# exp2_1.net
KiCad netlist of a schematic drawn in EAGLE
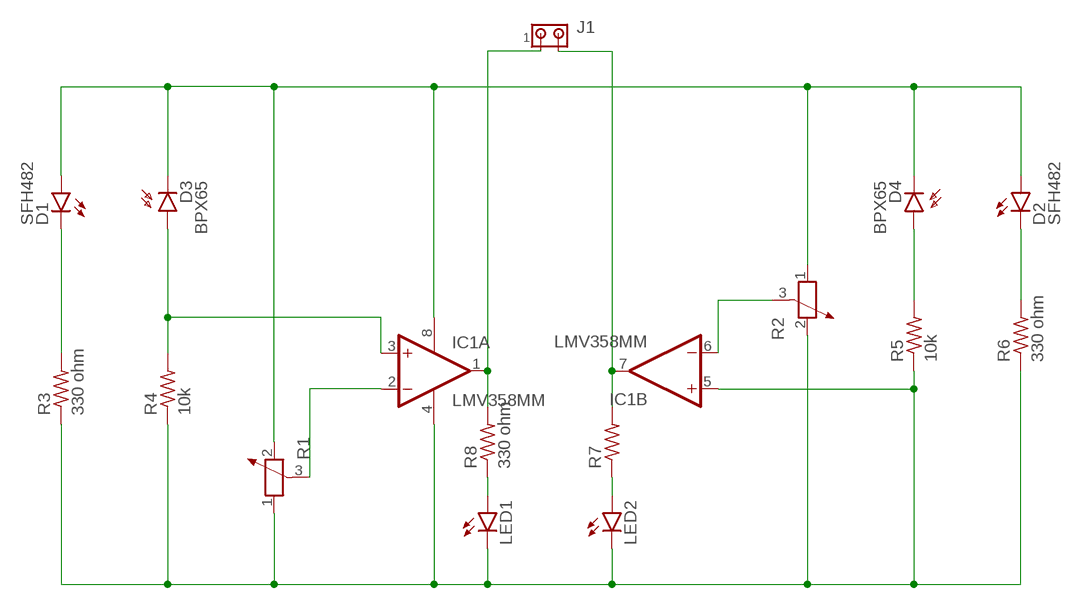
[diagram p0: schematic, sheet 1]

(export (version "E")
  (design (tool "Eeschema 10.0.6"))
  (components
    (comp (ref "D1")
      (value "SFH482")
      (footprint "eagle-import:SFH482")
      (libsource (lib "eagle-import") (part "SFH482"))
    )
    (comp (ref "D2")
      (value "SFH482")
      (footprint "eagle-import:SFH482")
      (libsource (lib "eagle-import") (part "SFH482"))
    )
    (comp (ref "D3")
      (value "BPX65")
      (footprint "eagle-import:BPX65")
      (fields (field (name "MPN") "BPX65."))
      (libsource (lib "eagle-import") (part "BPX65"))
    )
    (comp (ref "D4")
      (value "BPX65")
      (footprint "eagle-import:BPX65")
      (fields (field (name "MPN") "BPX65."))
      (libsource (lib "eagle-import") (part "BPX65"))
    )
    (comp (ref "IC1")
      (value "LMV358MM")
      (footprint "eagle-import:MSOP08")
      (libsource (lib "eagle-import") (part "LMV358?MM"))
    )
    (comp (ref "J1")
      (value "MTA02-100")
      (footprint "eagle-import:10X02MTA")
      (libsource (lib "eagle-import") (part "MTA02-100"))
    )
    (comp (ref "LED1")
      (value "LED3MM")
      (footprint "eagle-import:LED3MM")
      (libsource (lib "eagle-import") (part "LED3MM"))
    )
    (comp (ref "LED2")
      (value "LED3MM")
      (footprint "eagle-import:LED3MM")
      (libsource (lib "eagle-import") (part "LED3MM"))
    )
    (comp (ref "R1")
      (value "POTENTIOMETER_PT-10")
      (footprint "eagle-import:PT-10")
      (libsource (lib "eagle-import") (part "POTENTIOMETER_PT-10"))
    )
    (comp (ref "R2")
      (value "POTENTIOMETER_PT-10")
      (footprint "eagle-import:PT-10")
      (libsource (lib "eagle-import") (part "POTENTIOMETER_PT-10"))
    )
    (comp (ref "R3")
      (value "330 ohm")
      (footprint "eagle-import:0207_10")
      (libsource (lib "eagle-import") (part "R-US_0207/10"))
    )
    (comp (ref "R4")
      (value "10k")
      (footprint "eagle-import:0207_10")
      (libsource (lib "eagle-import") (part "R-US_0207/10"))
    )
    (comp (ref "R5")
      (value "10k")
      (footprint "eagle-import:0207_10")
      (libsource (lib "eagle-import") (part "R-US_0207/10"))
    )
    (comp (ref "R6")
      (value "330 ohm")
      (footprint "eagle-import:0207_10")
      (libsource (lib "eagle-import") (part "R-US_0207/10"))
    )
    (comp (ref "R7")
      (value "R-US_0207/10")
      (footprint "eagle-import:0207_10")
      (libsource (lib "eagle-import") (part "R-US_0207/10"))
    )
    (comp (ref "R8")
      (value "330 ohm")
      (footprint "eagle-import:0207_10")
      (libsource (lib "eagle-import") (part "R-US_0207/10"))
    )
  )
  (nets
    (net (code "1") (name "Net-(D1-C)") (class "Default")
      (node (ref "D1") (pin "K") (pinfunction "C_K") (pintype "passive"))
      (node (ref "R3") (pin "2") (pinfunction "2_2") (pintype "passive"))
    )
    (net (code "2") (name "Net-(D2-C)") (class "Default")
      (node (ref "D2") (pin "K") (pinfunction "C_K") (pintype "passive"))
      (node (ref "R6") (pin "2") (pinfunction "2_2") (pintype "passive"))
    )
    (net (code "3") (name "Net-(D3-C)") (class "Default")
      (node (ref "D1") (pin "A") (pinfunction "A_A") (pintype "passive"))
      (node (ref "D2") (pin "A") (pinfunction "A_A") (pintype "passive"))
      (node (ref "D3") (pin "K") (pinfunction "C_K") (pintype "passive"))
      (node (ref "D4") (pin "K") (pinfunction "C_K") (pintype "passive"))
      (node (ref "IC1") (pin "8") (pinfunction "V+_8") (pintype "power_in"))
      (node (ref "R1") (pin "2") (pinfunction "2_2") (pintype "passive"))
      (node (ref "R2") (pin "1") (pinfunction "1_1") (pintype "passive"))
    )
    (net (code "4") (name "Net-(D4-PadA)") (class "Default")
      (node (ref "D4") (pin "A") (pinfunction "A_A") (pintype "passive"))
      (node (ref "R5") (pin "2") (pinfunction "2_2") (pintype "passive"))
    )
    (net (code "5") (name "Net-(IC1A-+IN)") (class "Default")
      (node (ref "D3") (pin "A") (pinfunction "A_A") (pintype "passive"))
      (node (ref "IC1") (pin "3") (pinfunction "+IN_3") (pintype "input"))
      (node (ref "R4") (pin "2") (pinfunction "2_2") (pintype "passive"))
    )
    (net (code "6") (name "Net-(IC1A--IN)") (class "Default")
      (node (ref "IC1") (pin "2") (pinfunction "-IN_2") (pintype "input"))
      (node (ref "R1") (pin "3") (pinfunction "3_3") (pintype "passive"))
    )
    (net (code "7") (name "Net-(IC1A-OUT)") (class "Default")
      (node (ref "IC1") (pin "1") (pinfunction "OUT_1") (pintype "output"))
      (node (ref "J1") (pin "1") (pinfunction "1_1") (pintype "passive"))
      (node (ref "R8") (pin "2") (pinfunction "2_2") (pintype "passive"))
    )
    (net (code "8") (name "Net-(IC1B-+IN)") (class "Default")
      (node (ref "IC1") (pin "4") (pinfunction "V-_4") (pintype "power_in"))
      (node (ref "IC1") (pin "5") (pinfunction "+IN_5") (pintype "input"))
      (node (ref "LED1") (pin "K") (pinfunction "C_K") (pintype "passive"))
      (node (ref "LED2") (pin "K") (pinfunction "C_K") (pintype "passive"))
      (node (ref "R1") (pin "1") (pinfunction "1_1") (pintype "passive"))
      (node (ref "R2") (pin "2") (pinfunction "2_2") (pintype "passive"))
      (node (ref "R3") (pin "1") (pinfunction "1_1") (pintype "passive"))
      (node (ref "R4") (pin "1") (pinfunction "1_1") (pintype "passive"))
      (node (ref "R5") (pin "1") (pinfunction "1_1") (pintype "passive"))
      (node (ref "R6") (pin "1") (pinfunction "1_1") (pintype "passive"))
    )
    (net (code "9") (name "Net-(IC1B--IN)") (class "Default")
      (node (ref "IC1") (pin "6") (pinfunction "-IN_6") (pintype "input"))
      (node (ref "R2") (pin "3") (pinfunction "3_3") (pintype "passive"))
    )
    (net (code "10") (name "Net-(IC1B-OUT)") (class "Default")
      (node (ref "IC1") (pin "7") (pinfunction "OUT_7") (pintype "output"))
      (node (ref "J1") (pin "2") (pinfunction "2_2") (pintype "passive"))
      (node (ref "R7") (pin "2") (pinfunction "2_2") (pintype "passive"))
    )
    (net (code "11") (name "Net-(LED1-PadA)") (class "Default")
      (node (ref "LED1") (pin "A") (pinfunction "A_A") (pintype "passive"))
      (node (ref "R8") (pin "1") (pinfunction "1_1") (pintype "passive"))
    )
    (net (code "12") (name "Net-(LED2-PadA)") (class "Default")
      (node (ref "LED2") (pin "A") (pinfunction "A_A") (pintype "passive"))
      (node (ref "R7") (pin "1") (pinfunction "1_1") (pintype "passive"))
    )
  )
)
